# SparkFun_Infrared_Sensor_STH34PF80.net
KiCad netlist of a schematic drawn in EAGLE
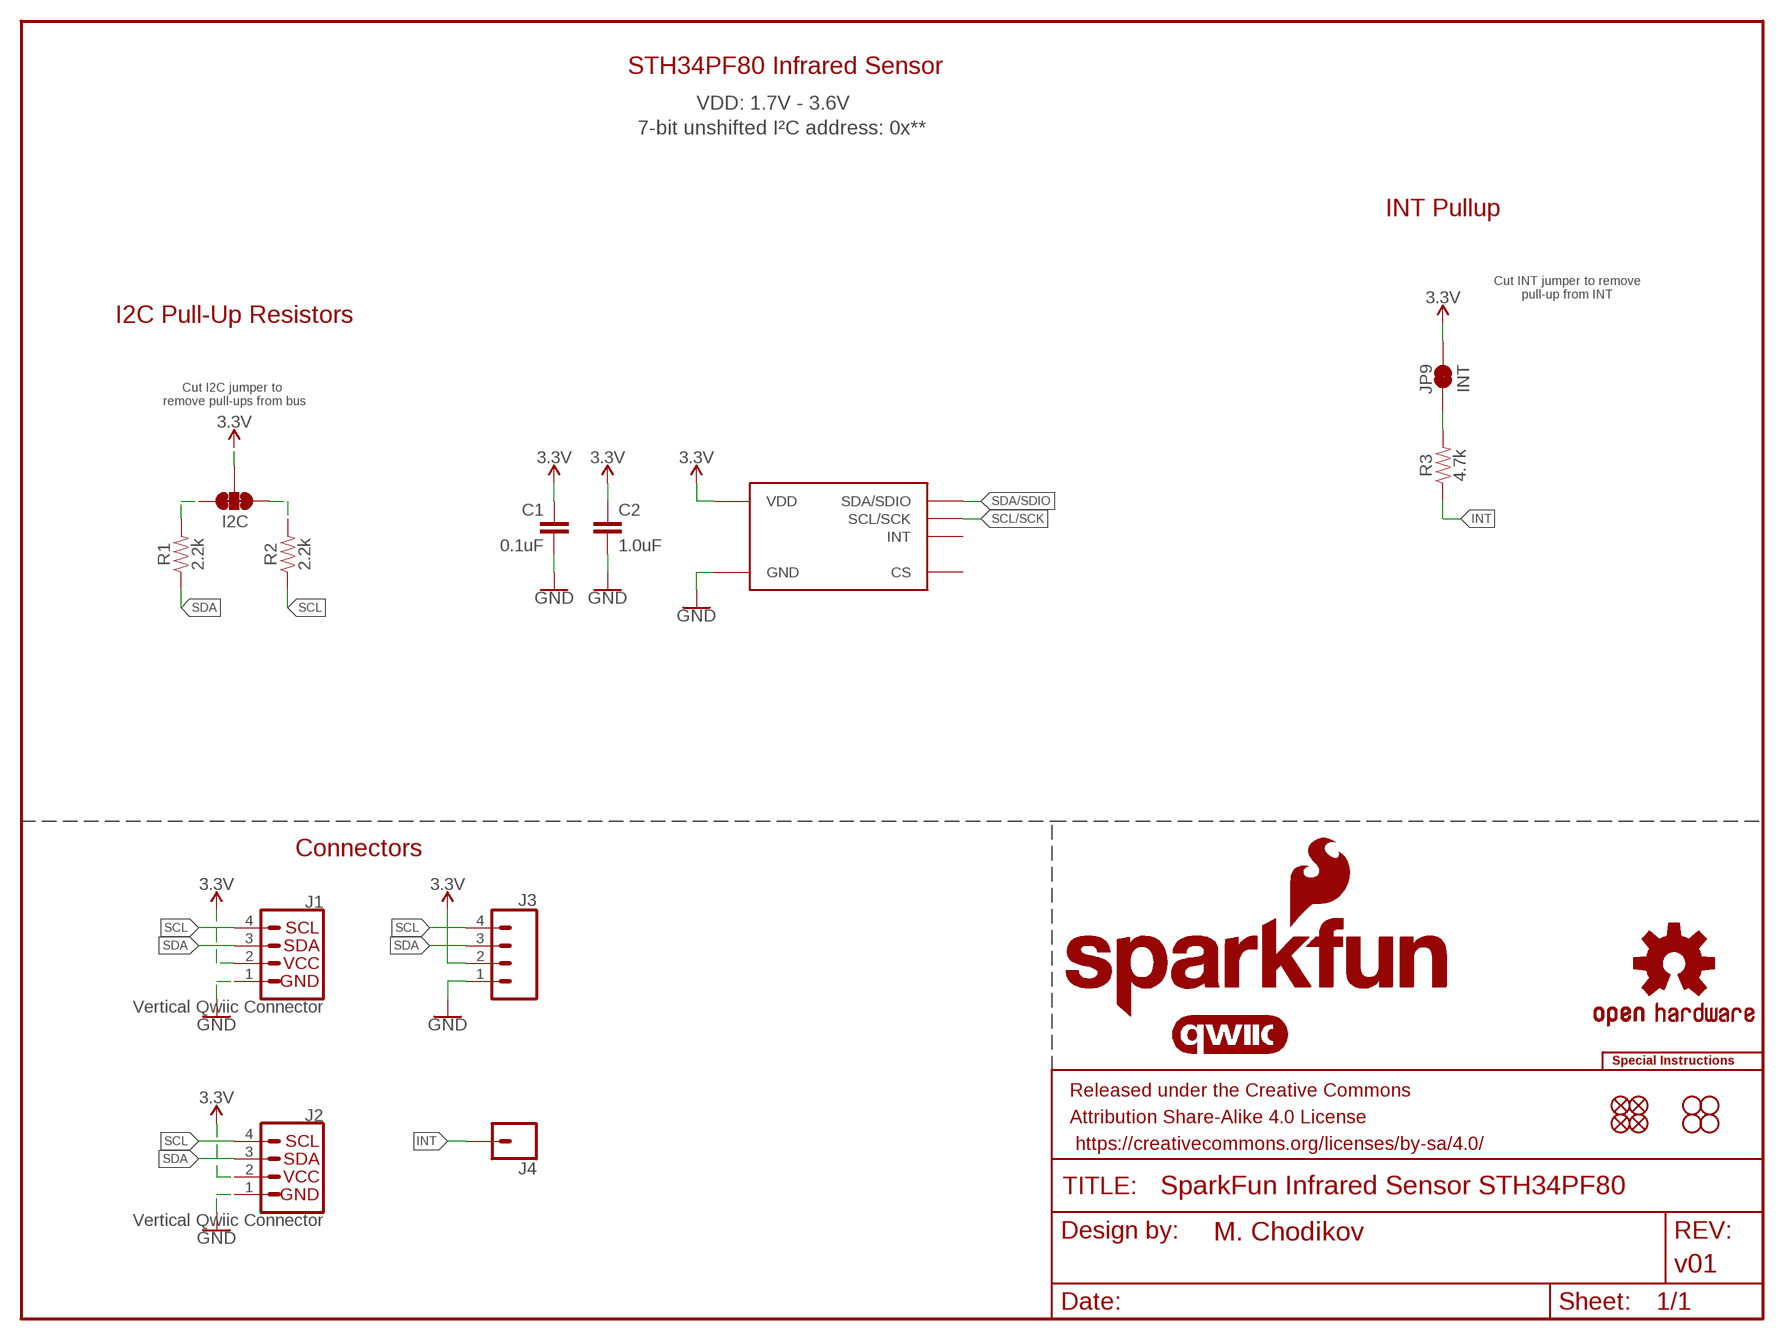
[diagram p0: schematic, sheet 1]

(export (version "E")
  (design (tool "Eeschema 10.0.6"))
  (components
    (comp (ref "C1")
      (value "0.1uF")
      (footprint "eagle-import:0603")
      (libsource (lib "eagle-import") (part "0.1UF-0603-25V-10%-X7R-WE"))
    )
    (comp (ref "C2")
      (value "1.0uF")
      (footprint "eagle-import:0603")
      (libsource (lib "eagle-import") (part "1.0UF-0603-16V-10%-X7R"))
    )
    (comp (ref "FRAME1")
      (value "FRAME-LETTER")
      (footprint "eagle-import:CREATIVE_COMMONS")
      (fields (field (name "DESIGNER") "M. Chodikov") (field (name "REV") "v01"))
      (libsource (lib "eagle-import") (part "FRAME-LETTER"))
    )
    (comp (ref "I2C")
      (value "JUMPER-SMT_3_2-NC_TRACE_SILK")
      (footprint "eagle-import:SMT-JUMPER_3_2-NC_TRACE_SILK")
      (libsource (lib "eagle-import") (part "JUMPER-SMT_3_2-NC_TRACE_SILK"))
    )
    (comp (ref "J1")
      (value "Vertical Qwiic Connector")
      (footprint "eagle-import:JST04_1MM_VERT")
      (libsource (lib "eagle-import") (part "QWIIC_CONNECTOR"))
    )
    (comp (ref "J2")
      (value "Vertical Qwiic Connector")
      (footprint "eagle-import:JST04_1MM_VERT")
      (libsource (lib "eagle-import") (part "QWIIC_CONNECTOR"))
    )
    (comp (ref "J3")
      (value "CONN_041X04_NO_SILK")
      (footprint "eagle-import:1X04_NO_SILK")
      (libsource (lib "eagle-import") (part "CONN_041X04_NO_SILK"))
    )
    (comp (ref "J4")
      (value "CONN_01PTH_NO_SILK_YES_STOP")
      (footprint "eagle-import:1X01_NO_SILK")
      (libsource (lib "eagle-import") (part "CONN_01PTH_NO_SILK_YES_STOP"))
    )
    (comp (ref "JP1")
      (value "FIDUCIALUFIDUCIAL")
      (footprint "eagle-import:FIDUCIAL-MICRO")
      (libsource (lib "eagle-import") (part "FIDUCIALUFIDUCIAL"))
    )
    (comp (ref "JP2")
      (value "FIDUCIALUFIDUCIAL")
      (footprint "eagle-import:FIDUCIAL-MICRO")
      (libsource (lib "eagle-import") (part "FIDUCIALUFIDUCIAL"))
    )
    (comp (ref "JP3")
      (value "STAND-OFF")
      (footprint "eagle-import:STAND-OFF")
      (libsource (lib "eagle-import") (part "STAND-OFF"))
    )
    (comp (ref "JP4")
      (value "STAND-OFF")
      (footprint "eagle-import:STAND-OFF")
      (libsource (lib "eagle-import") (part "STAND-OFF"))
    )
    (comp (ref "JP5")
      (value "FIDUCIALUFIDUCIAL")
      (footprint "eagle-import:FIDUCIAL-MICRO")
      (libsource (lib "eagle-import") (part "FIDUCIALUFIDUCIAL"))
    )
    (comp (ref "JP6")
      (value "FIDUCIALUFIDUCIAL")
      (footprint "eagle-import:FIDUCIAL-MICRO")
      (libsource (lib "eagle-import") (part "FIDUCIALUFIDUCIAL"))
    )
    (comp (ref "JP9")
      (value "INT")
      (footprint "eagle-import:SMT-JUMPER_2_NC_TRACE_SILK")
      (libsource (lib "eagle-import") (part "JUMPER-SMT_2_NC_TRACE_SILK"))
    )
    (comp (ref "JP10")
      (value "STAND-OFF")
      (footprint "eagle-import:STAND-OFF")
      (libsource (lib "eagle-import") (part "STAND-OFF"))
    )
    (comp (ref "JP11")
      (value "STAND-OFF")
      (footprint "eagle-import:STAND-OFF")
      (libsource (lib "eagle-import") (part "STAND-OFF"))
    )
    (comp (ref "LOGO1")
      (value "SFE_LOGO_NAME_FLAME8_MM")
      (footprint "eagle-import:SFE_LOGO_NAME_FLAME_8MM")
      (libsource (lib "eagle-import") (part "SFE_LOGO_NAME_FLAME8_MM"))
    )
    (comp (ref "LOGO2")
      (value "OSHW-LOGONO_SILK")
      (footprint "eagle-import:DUMMY")
      (libsource (lib "eagle-import") (part "OSHW-LOGONO_SILK"))
    )
    (comp (ref "LOGO3")
      (value "QWIIC_LOGO_CONNECTOR")
      (footprint "eagle-import:QWIIC_5.5MM")
      (libsource (lib "eagle-import") (part "QWIIC_LOGO_CONNECTOR"))
    )
    (comp (ref "LOGO4")
      (value "SFE_LOGO_NAME6_MM")
      (footprint "eagle-import:SFE_LOGO_NAME_6MM")
      (libsource (lib "eagle-import") (part "SFE_LOGO_NAME6_MM"))
    )
    (comp (ref "LOGO5")
      (value "SPECIAL_INSTRUCTIONS-ORDERING")
      (footprint "eagle-import:ORDERING_INSTRUCTIONS")
      (libsource (lib "eagle-import") (part "SPECIAL_INSTRUCTIONS-ORDERING"))
    )
    (comp (ref "R1")
      (value "2.2k")
      (footprint "eagle-import:0603")
      (libsource (lib "eagle-import") (part "2.2KOHM-0603-1/10W-1%"))
    )
    (comp (ref "R2")
      (value "2.2k")
      (footprint "eagle-import:0603")
      (libsource (lib "eagle-import") (part "2.2KOHM-0603-1/10W-1%"))
    )
    (comp (ref "R3")
      (value "4.7k")
      (footprint "eagle-import:0603")
      (libsource (lib "eagle-import") (part "4.7KOHM-0603-1/10W-1%"))
    )
    (comp (ref "U$1")
      (value "STHS34PF80")
      (footprint "eagle-import:LGA-10L")
      (libsource (lib "eagle-import") (part "STHS34PF80"))
    )
  )
  (nets
    (net (code "1") (name "3.3V") (class "Default")
      (node (ref "C1") (pin "1") (pinfunction "1_1") (pintype "passive"))
      (node (ref "C2") (pin "1") (pinfunction "1_1") (pintype "passive"))
      (node (ref "I2C") (pin "2") (pinfunction "2_2") (pintype "passive"))
      (node (ref "J1") (pin "2") (pinfunction "2_2") (pintype "power_in"))
      (node (ref "J2") (pin "2") (pinfunction "2_2") (pintype "power_in"))
      (node (ref "J3") (pin "2") (pinfunction "2_2") (pintype "passive"))
      (node (ref "JP9") (pin "2") (pinfunction "2_2") (pintype "passive"))
      (node (ref "U$1") (pin "6") (pinfunction "VDD_6") (pintype "bidirectional"))
      (node (ref "U$1") (pin "9") (pinfunction "VDD_9") (pintype "bidirectional"))
    )
    (net (code "2") (name "GND") (class "Default")
      (node (ref "C1") (pin "2") (pinfunction "2_2") (pintype "passive"))
      (node (ref "C2") (pin "2") (pinfunction "2_2") (pintype "passive"))
      (node (ref "J1") (pin "1") (pinfunction "1_1") (pintype "power_in"))
      (node (ref "J2") (pin "1") (pinfunction "1_1") (pintype "power_in"))
      (node (ref "J3") (pin "1") (pinfunction "1_1") (pintype "passive"))
      (node (ref "U$1") (pin "2") (pinfunction "GND_2") (pintype "bidirectional"))
      (node (ref "U$1") (pin "7") (pinfunction "GND_7") (pintype "bidirectional"))
      (node (ref "U$1") (pin "8") (pinfunction "GND_8") (pintype "bidirectional"))
    )
    (net (code "3") (name "INT") (class "Default")
      (node (ref "J4") (pin "1") (pinfunction "1_1") (pintype "passive"))
      (node (ref "R3") (pin "1") (pinfunction "1_1") (pintype "passive"))
    )
    (net (code "4") (name "Net-(I2C-Pad1)") (class "Default")
      (node (ref "I2C") (pin "1") (pinfunction "1_1") (pintype "passive"))
      (node (ref "R2") (pin "2") (pinfunction "2_2") (pintype "passive"))
    )
    (net (code "5") (name "Net-(I2C-Pad3)") (class "Default")
      (node (ref "I2C") (pin "3") (pinfunction "3_3") (pintype "passive"))
      (node (ref "R1") (pin "2") (pinfunction "2_2") (pintype "passive"))
    )
    (net (code "6") (name "Net-(JP9-Pad1)") (class "Default")
      (node (ref "JP9") (pin "1") (pinfunction "1_1") (pintype "passive"))
      (node (ref "R3") (pin "2") (pinfunction "2_2") (pintype "passive"))
    )
    (net (code "7") (name "SCL") (class "Default")
      (node (ref "J1") (pin "4") (pinfunction "4_4") (pintype "passive"))
      (node (ref "J2") (pin "4") (pinfunction "4_4") (pintype "passive"))
      (node (ref "J3") (pin "4") (pinfunction "4_4") (pintype "passive"))
      (node (ref "R2") (pin "1") (pinfunction "1_1") (pintype "passive"))
    )
    (net (code "8") (name "SCL{slash}SCK") (class "Default")
      (node (ref "U$1") (pin "1") (pinfunction "SCL/SCK_1") (pintype "bidirectional"))
    )
    (net (code "9") (name "SDA") (class "Default")
      (node (ref "J1") (pin "3") (pinfunction "3_3") (pintype "passive"))
      (node (ref "J2") (pin "3") (pinfunction "3_3") (pintype "passive"))
      (node (ref "J3") (pin "3") (pinfunction "3_3") (pintype "passive"))
      (node (ref "R1") (pin "1") (pinfunction "1_1") (pintype "passive"))
    )
    (net (code "10") (name "SDA{slash}SDIO") (class "Default")
      (node (ref "U$1") (pin "4") (pinfunction "SDA/SDIO_4") (pintype "bidirectional"))
    )
    (net (code "11") (name "unconnected-(U$1-CS-Pad3)") (class "Default")
      (node (ref "U$1") (pin "3") (pinfunction "CS_3") (pintype "bidirectional"))
    )
    (net (code "12") (name "unconnected-(U$1-INT-Pad10)") (class "Default")
      (node (ref "U$1") (pin "10") (pinfunction "INT_10") (pintype "bidirectional"))
    )
  )
)
